# Quad_FC_V10_3.net
KiCad netlist of a schematic drawn in Altium Designer
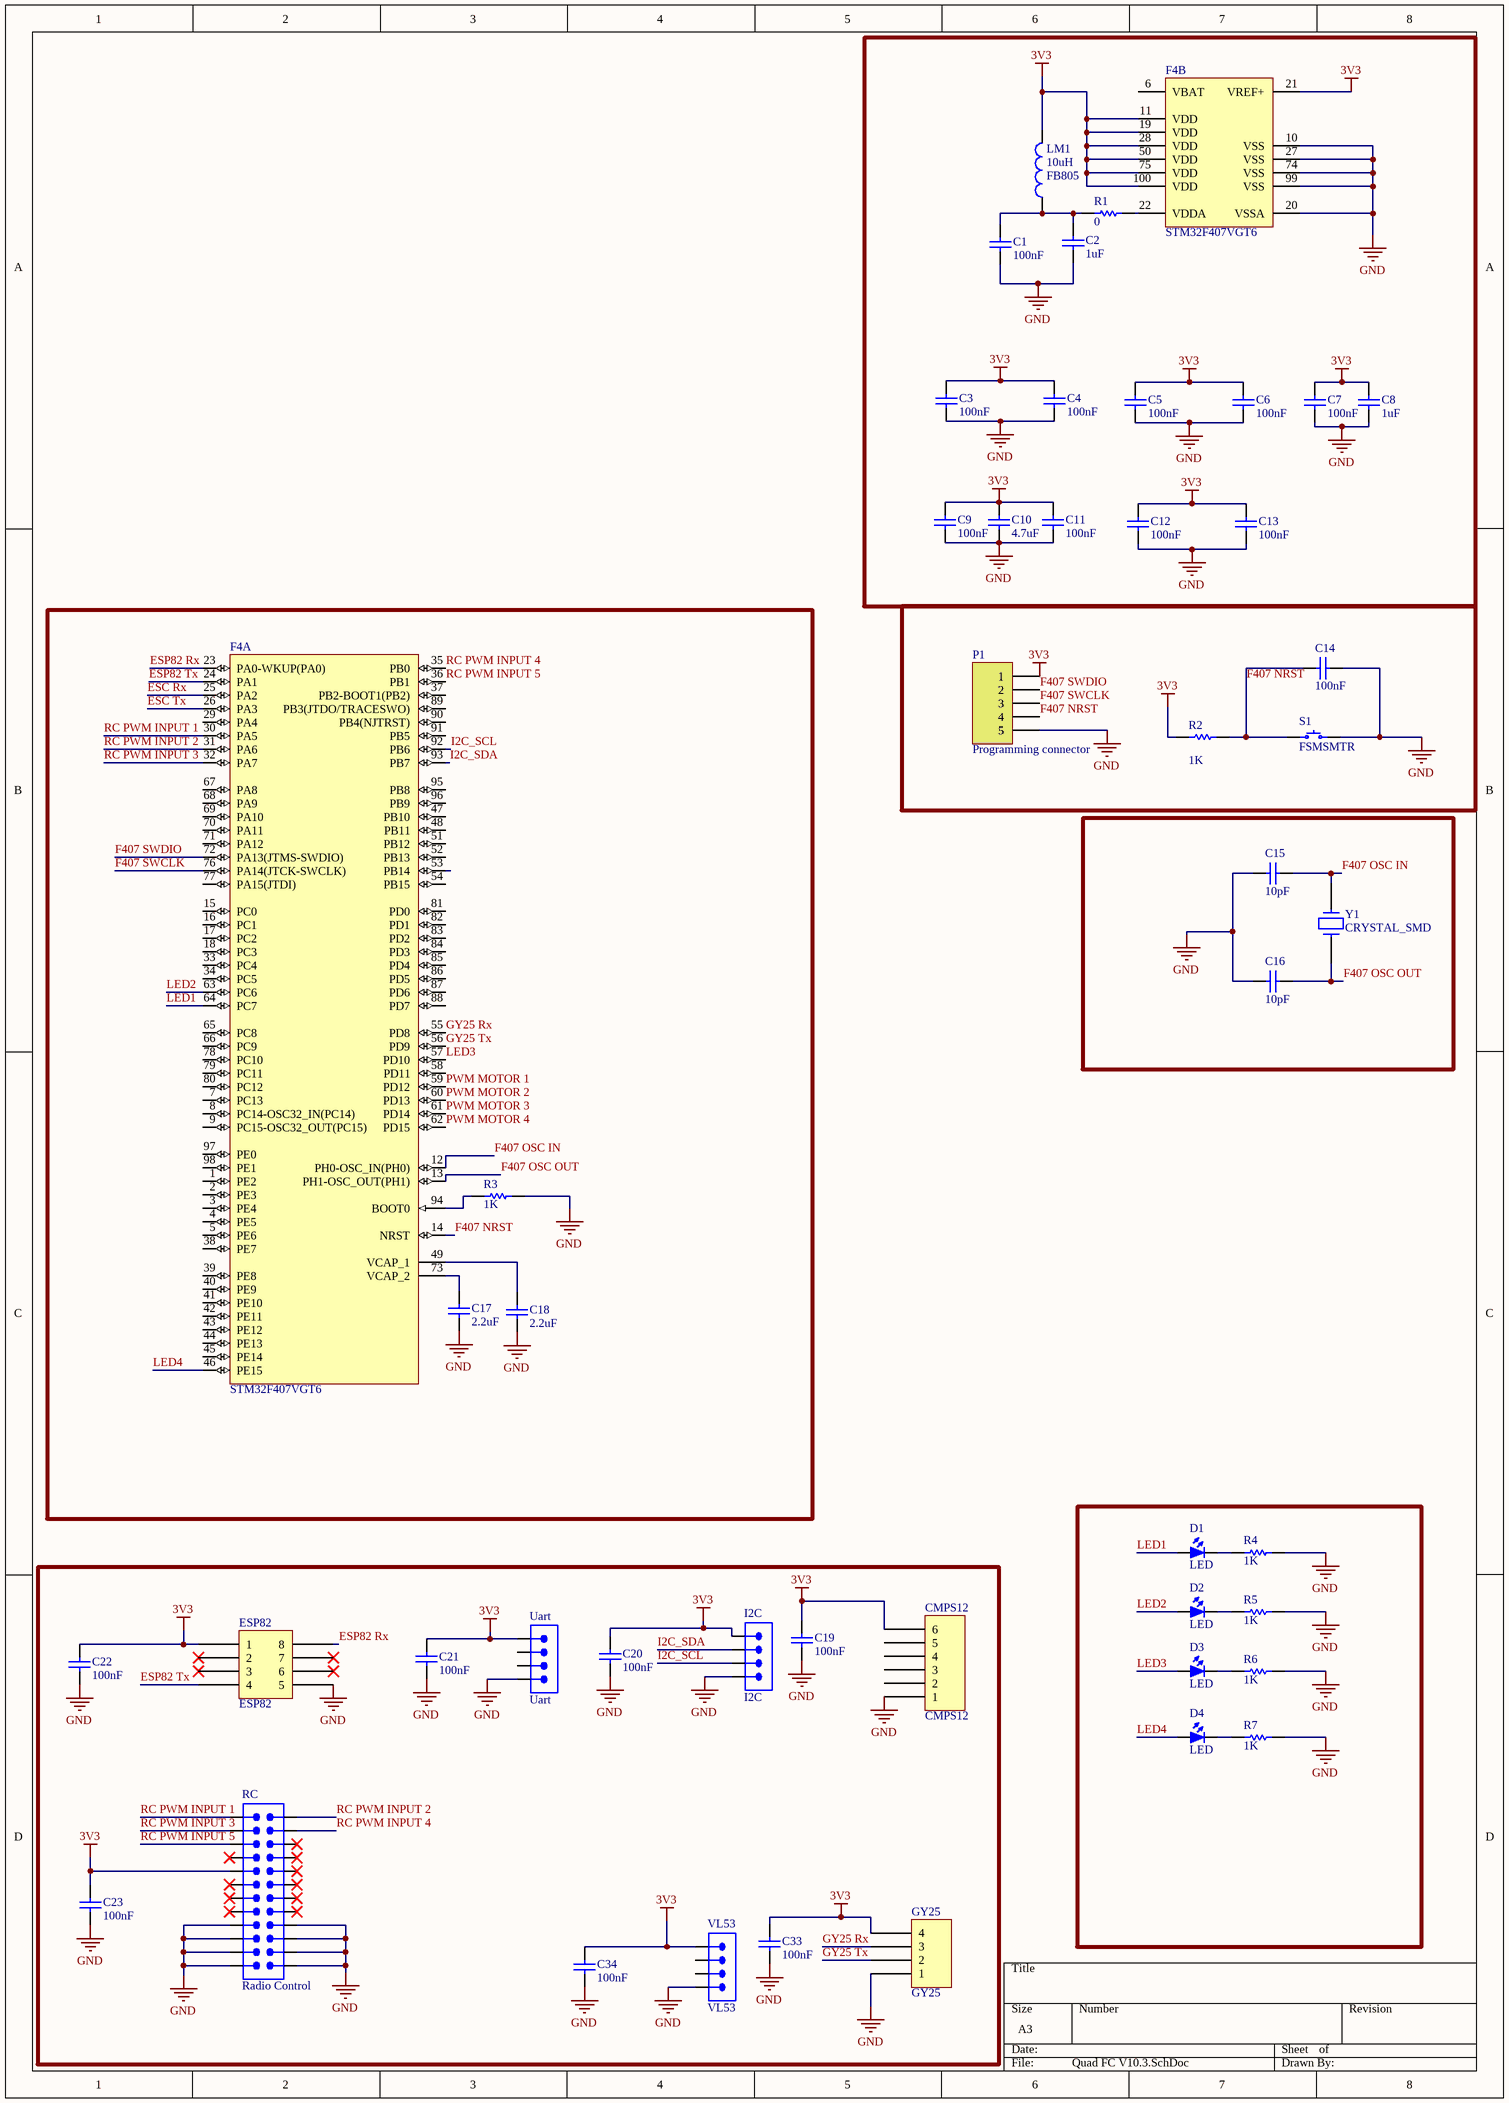
[diagram p0: Quad FC V10.3.SchDoc]

(export (version "E")
  (design (tool "Eeschema 10.0.6"))
  (components
    (comp (ref "C1")
      (value "100nF")
      (footprint "CAP0603")
      (description "F407VET6 Power CAP")
      (fields (field (name "DESIGNER") "Abbas Basereh"))
      (libsource (lib "2017AbbasBasereh9365731239 -ver1") (part "CAP SMD PACKAGE"))
    )
    (comp (ref "C2")
      (value "1uF")
      (footprint "CAP0603")
      (description "F407VET6 Power CAP")
      (fields (field (name "DESIGNER") "Abbas Basereh"))
      (libsource (lib "2017AbbasBasereh9365731239 -ver1") (part "CAP SMD PACKAGE"))
    )
    (comp (ref "C3")
      (value "100nF")
      (footprint "CAP0603")
      (description "F407VET6 Power CAP")
      (fields (field (name "DESIGNER") "Abbas Basereh"))
      (libsource (lib "2017AbbasBasereh9365731239 -ver1") (part "CAP SMD PACKAGE"))
    )
    (comp (ref "C4")
      (value "100nF")
      (footprint "CAP0603")
      (description "F407VET6 Power CAP")
      (fields (field (name "DESIGNER") "Abbas Basereh"))
      (libsource (lib "2017AbbasBasereh9365731239 -ver1") (part "CAP SMD PACKAGE"))
    )
    (comp (ref "C5")
      (value "100nF")
      (footprint "CAP0603")
      (description "F407VET6 Power CAP")
      (fields (field (name "DESIGNER") "Abbas Basereh"))
      (libsource (lib "2017AbbasBasereh9365731239 -ver1") (part "CAP SMD PACKAGE"))
    )
    (comp (ref "C6")
      (value "100nF")
      (footprint "CAP0603")
      (description "F407VET6 Power CAP")
      (fields (field (name "DESIGNER") "Abbas Basereh"))
      (libsource (lib "2017AbbasBasereh9365731239 -ver1") (part "CAP SMD PACKAGE"))
    )
    (comp (ref "C7")
      (value "100nF")
      (footprint "CAP0603")
      (description "F407VET6 Power CAP")
      (fields (field (name "DESIGNER") "Abbas Basereh"))
      (libsource (lib "2017AbbasBasereh9365731239 -ver1") (part "CAP SMD PACKAGE"))
    )
    (comp (ref "C8")
      (value "1uF")
      (footprint "CAP0603")
      (description "F407VET6 Power CAP")
      (fields (field (name "DESIGNER") "Abbas Basereh"))
      (libsource (lib "2017AbbasBasereh9365731239 -ver1") (part "CAP SMD PACKAGE"))
    )
    (comp (ref "C9")
      (value "100nF")
      (footprint "CAP0603")
      (description "F407VET6 Power CAP")
      (fields (field (name "DESIGNER") "Abbas Basereh"))
      (libsource (lib "2017AbbasBasereh9365731239 -ver1") (part "CAP SMD PACKAGE"))
    )
    (comp (ref "C10")
      (value "4.7uF")
      (footprint "CAP0603")
      (description "F407VET6 Power CAP")
      (fields (field (name "DESIGNER") "Abbas Basereh"))
      (libsource (lib "2017AbbasBasereh9365731239 -ver1") (part "CAP SMD PACKAGE"))
    )
    (comp (ref "C11")
      (value "100nF")
      (footprint "CAP0603")
      (description "F407VET6 Power CAP")
      (fields (field (name "DESIGNER") "Abbas Basereh"))
      (libsource (lib "2017AbbasBasereh9365731239 -ver1") (part "CAP SMD PACKAGE"))
    )
    (comp (ref "C12")
      (value "100nF")
      (footprint "CAP0603")
      (description "F407VET6 Power CAP")
      (fields (field (name "DESIGNER") "Abbas Basereh"))
      (libsource (lib "2017AbbasBasereh9365731239 -ver1") (part "CAP SMD PACKAGE"))
    )
    (comp (ref "C13")
      (value "100nF")
      (footprint "CAP0603")
      (description "F407VET6 Power CAP")
      (fields (field (name "DESIGNER") "Abbas Basereh"))
      (libsource (lib "2017AbbasBasereh9365731239 -ver1") (part "CAP SMD PACKAGE"))
    )
    (comp (ref "C14")
      (value "100nF")
      (footprint "CAP0603")
      (description "F407VET6 Power CAP")
      (fields (field (name "DESIGNER") "Abbas Basereh"))
      (libsource (lib "2017AbbasBasereh9365731239 -ver1") (part "CAP SMD PACKAGE"))
    )
    (comp (ref "C15")
      (value "10pF")
      (footprint "CAP0603")
      (description "F407VET6 Power CAP")
      (fields (field (name "DESIGNER") "Abbas Basereh"))
      (libsource (lib "2017AbbasBasereh9365731239 -ver1") (part "CAP SMD PACKAGE"))
    )
    (comp (ref "C16")
      (value "10pF")
      (footprint "CAP0603")
      (description "F407VET6 Power CAP")
      (fields (field (name "DESIGNER") "Abbas Basereh"))
      (libsource (lib "2017AbbasBasereh9365731239 -ver1") (part "CAP SMD PACKAGE"))
    )
    (comp (ref "C17")
      (value "2.2uF")
      (footprint "CAP0603")
      (description "F407VET6 Power CAP")
      (fields (field (name "DESIGNER") "Abbas Basereh"))
      (libsource (lib "2017AbbasBasereh9365731239 -ver1") (part "CAP SMD PACKAGE"))
    )
    (comp (ref "C18")
      (value "2.2uF")
      (footprint "CAP0603")
      (description "F407VET6 Power CAP")
      (fields (field (name "DESIGNER") "Abbas Basereh"))
      (libsource (lib "2017AbbasBasereh9365731239 -ver1") (part "CAP SMD PACKAGE"))
    )
    (comp (ref "C19")
      (value "100nF")
      (footprint "CAP0603")
      (description "F407VET6 Power CAP")
      (fields (field (name "DESIGNER") "Abbas Basereh"))
      (libsource (lib "2017AbbasBasereh9365731239 -ver1") (part "CAP SMD PACKAGE"))
    )
    (comp (ref "C20")
      (value "100nF")
      (footprint "CAP0603")
      (description "F407VET6 Power CAP")
      (fields (field (name "DESIGNER") "Abbas Basereh"))
      (libsource (lib "2017AbbasBasereh9365731239 -ver1") (part "CAP SMD PACKAGE"))
    )
    (comp (ref "C21")
      (value "100nF")
      (footprint "CAP0603")
      (description "F407VET6 Power CAP")
      (fields (field (name "DESIGNER") "Abbas Basereh"))
      (libsource (lib "2017AbbasBasereh9365731239 -ver1") (part "CAP SMD PACKAGE"))
    )
    (comp (ref "C22")
      (value "100nF")
      (footprint "CAP0603")
      (description "F407VET6 Power CAP")
      (fields (field (name "DESIGNER") "Abbas Basereh"))
      (libsource (lib "2017AbbasBasereh9365731239 -ver1") (part "CAP SMD PACKAGE"))
    )
    (comp (ref "C23")
      (value "100nF")
      (footprint "CAP0603")
      (description "F407VET6 Power CAP")
      (fields (field (name "DESIGNER") "Abbas Basereh"))
      (libsource (lib "2017AbbasBasereh9365731239 -ver1") (part "CAP SMD PACKAGE"))
    )
    (comp (ref "C33")
      (value "100nF")
      (footprint "CAP0603")
      (description "F407VET6 Power CAP")
      (fields (field (name "DESIGNER") "Abbas Basereh"))
      (libsource (lib "2017AbbasBasereh9365731239 -ver1") (part "CAP SMD PACKAGE"))
    )
    (comp (ref "C34")
      (value "100nF")
      (footprint "CAP0603")
      (description "F407VET6 Power CAP")
      (fields (field (name "DESIGNER") "Abbas Basereh"))
      (libsource (lib "2017AbbasBasereh9365731239 -ver1") (part "CAP SMD PACKAGE"))
    )
    (comp (ref "CMPS12")
      (value "CMPS12")
      (footprint "SAMTEC SSW-106-03-T-S")
      (description "CONN RCPT 6POS 0.1 TIN PCB")
      (fields (field (name "PART NUMBER") "SSW-106-03-T-S") (field (name "MANUFACTURER") "Samtec Inc."))
      (libsource (lib "Celestial Altium Library - altium_library (1)") (part "6 Pin"))
    )
    (comp (ref "D1")
      (value "LED")
      (footprint "0603 - LED")
      (description "Led")
      (fields (field (name "PUBLISHER") "Altium Limited"))
      (libsource (lib "Sajad_Altium_Library") (part "LED"))
    )
    (comp (ref "D2")
      (value "LED")
      (footprint "0603 - LED")
      (description "Led")
      (fields (field (name "PUBLISHER") "Altium Limited"))
      (libsource (lib "Sajad_Altium_Library") (part "LED"))
    )
    (comp (ref "D3")
      (value "LED")
      (footprint "0603 - LED")
      (description "Led")
      (fields (field (name "PUBLISHER") "Altium Limited"))
      (libsource (lib "Sajad_Altium_Library") (part "LED"))
    )
    (comp (ref "D4")
      (value "LED")
      (footprint "0603 - LED")
      (description "Led")
      (fields (field (name "PUBLISHER") "Altium Limited"))
      (libsource (lib "Sajad_Altium_Library") (part "LED"))
    )
    (comp (ref "ESP82")
      (value "ESP82")
      (footprint "HARWIN M20-7830445")
      (description "CONN RCPT 8POS 0.1 GOLD PCB")
      (fields (field (name "PART NUMBER") "M20-7830442") (field (name "MANUFACTURER") "Harwin Inc."))
      (libsource (lib "Celestial Altium Library - altium_library (1)") (part "2X4 PIN DU"))
    )
    (comp (ref "F4")
      (value "STM32F407VGT6")
      (footprint "STM-LQFP100_N")
      (fields (field (name "MANUFACTURER") "STMicroelectronics"))
      (libsource (lib "STMicroelectronics STM32 F4") (part "STM32F407VGT6"))
    )
    (comp (ref "GY25")
      (value "GY25")
      (footprint "SAMTEC SSW-104-03-T-S")
      (description "CONN RCPT 4POS 0.1 TIN PCB")
      (fields (field (name "PART NUMBER") "SSW-104-03-T-S") (field (name "MANUFACTURER") "Samtec Inc."))
      (libsource (lib "Celestial Altium Library - altium_library (1)") (part "4 Pin"))
    )
    (comp (ref "I2C")
      (value "I2C")
      (footprint "JST BM04B-SURS-TF")
      (description "Male Header 1X04")
      (libsource (lib "SJ Sockets & Connectors") (part "MHDR_1X04"))
    )
    (comp (ref "LM1")
      (value "10uH")
      (footprint "0805L")
      (description "Inductor")
      (fields (field (name "ALTIUM_VALUE") "FB805") (field (name "PUBLISHER") "Altium Limited"))
      (libsource (lib "2017AbbasBasereh9365731239 -ver1") (part "L SMA 0.25W"))
    )
    (comp (ref "P1")
      (value "Programming connector")
      (footprint "Connector1X5")
      (description "Connector, 5-Pin2.5mm")
      (fields (field (name "PUBLISHER") "Altium Limited"))
      (libsource (lib "Sajad_Altium_Library") (part "Connector1x5"))
    )
    (comp (ref "R1")
      (value "0")
      (footprint "RES0603")
      (description "TOTAL SMD RESISTOR PACK")
      (fields (field (name "DESIGNER") "Abbas Basereh"))
      (libsource (lib "2017AbbasBasereh9365731239 -ver1") (part "RES SMD PACKAGE"))
    )
    (comp (ref "R2")
      (value "1K")
      (footprint "RES0603")
      (description "TOTAL SMD RESISTOR PACK")
      (fields (field (name "DESIGNER") "Abbas Basereh"))
      (libsource (lib "2017AbbasBasereh9365731239 -ver1") (part "RES SMD PACKAGE"))
    )
    (comp (ref "R3")
      (value "1K")
      (footprint "RES0603")
      (description "TOTAL SMD RESISTOR PACK")
      (fields (field (name "DESIGNER") "Abbas Basereh"))
      (libsource (lib "2017AbbasBasereh9365731239 -ver1") (part "RES SMD PACKAGE"))
    )
    (comp (ref "R4")
      (value "1K")
      (footprint "RES0603")
      (description "TOTAL SMD RESISTOR PACK")
      (fields (field (name "DESIGNER") "Abbas Basereh"))
      (libsource (lib "2017AbbasBasereh9365731239 -ver1") (part "RES SMD PACKAGE"))
    )
    (comp (ref "R5")
      (value "1K")
      (footprint "RES0603")
      (description "TOTAL SMD RESISTOR PACK")
      (fields (field (name "DESIGNER") "Abbas Basereh"))
      (libsource (lib "2017AbbasBasereh9365731239 -ver1") (part "RES SMD PACKAGE"))
    )
    (comp (ref "R6")
      (value "1K")
      (footprint "RES0603")
      (description "TOTAL SMD RESISTOR PACK")
      (fields (field (name "DESIGNER") "Abbas Basereh"))
      (libsource (lib "2017AbbasBasereh9365731239 -ver1") (part "RES SMD PACKAGE"))
    )
    (comp (ref "R7")
      (value "1K")
      (footprint "RES0603")
      (description "TOTAL SMD RESISTOR PACK")
      (fields (field (name "DESIGNER") "Abbas Basereh"))
      (libsource (lib "2017AbbasBasereh9365731239 -ver1") (part "RES SMD PACKAGE"))
    )
    (comp (ref "RC")
      (value "Radio Control")
      (footprint "HEADER8X3:HEADER8X3")
      (description "Male Header 2X12")
      (libsource (lib "SJ Sockets & Connectors") (part "MHDR_2X12"))
    )
    (comp (ref "S1")
      (value "FSMSMTR")
      (footprint "TE FSMSMTR")
      (description "SWITCH TACTILE SPST-NO 0.05A 24V")
      (fields (field (name "MANUFACTURER") "TE Connectivity ALCOSWITCH Switches"))
      (libsource (lib "Celestial Altium Library - altium_library (1)") (part "SPST-NO 2 PIN"))
    )
    (comp (ref "Uart")
      (value "Uart")
      (footprint "JST BM04B-SURS-TF")
      (description "Male Header 1X04")
      (libsource (lib "SJ Sockets & Connectors") (part "MHDR_1X04"))
    )
    (comp (ref "VL53")
      (value "VL53")
      (footprint "JST BM04B-SURS-TF")
      (description "Male Header 1X04")
      (libsource (lib "SJ Sockets & Connectors") (part "MHDR_1X04"))
    )
    (comp (ref "Y1")
      (value "CRYSTAL_SMD")
      (footprint "My_Crystal - SMD")
      (description "Crystal")
      (libsource (lib "AMINLIB") (part "CRYSTAL_SMD"))
    )
  )
  (nets
    (net (code "1") (name "/ESC Rx") (class "Default")
      (node (ref "F4") (pin "25") (pinfunction "PA2_25") (pintype "bidirectional"))
    )
    (net (code "2") (name "/ESC Tx") (class "Default")
      (node (ref "F4") (pin "26") (pinfunction "PA3_26") (pintype "bidirectional"))
    )
    (net (code "3") (name "/ESP82 Rx") (class "Default")
      (node (ref "ESP82") (pin "8") (pinfunction "8_8") (pintype "passive"))
      (node (ref "F4") (pin "23") (pinfunction "PA0-WKUP(PA0)_23") (pintype "bidirectional"))
    )
    (net (code "4") (name "/ESP82 Tx") (class "Default")
      (node (ref "ESP82") (pin "4") (pinfunction "4_4") (pintype "passive"))
      (node (ref "F4") (pin "24") (pinfunction "PA1_24") (pintype "bidirectional"))
    )
    (net (code "5") (name "/F407 NRST") (class "Default")
      (node (ref "C14") (pin "1") (pinfunction "1_1") (pintype "passive"))
      (node (ref "F4") (pin "14") (pinfunction "NRST_14") (pintype "bidirectional"))
      (node (ref "P1") (pin "4") (pinfunction "4_4") (pintype "passive"))
      (node (ref "R2") (pin "2") (pinfunction "2_2") (pintype "passive"))
      (node (ref "S1") (pin "1") (pinfunction "1_1") (pintype "passive"))
    )
    (net (code "6") (name "/F407 OSC IN") (class "Default")
      (node (ref "C15") (pin "2") (pinfunction "2_2") (pintype "passive"))
      (node (ref "F4") (pin "12") (pinfunction "PH0-OSC_IN(PH0)_12") (pintype "bidirectional"))
      (node (ref "Y1") (pin "2") (pinfunction "2_2") (pintype "passive"))
    )
    (net (code "7") (name "/F407 OSC OUT") (class "Default")
      (node (ref "C16") (pin "1") (pinfunction "1_1") (pintype "passive"))
      (node (ref "F4") (pin "13") (pinfunction "PH1-OSC_OUT(PH1)_13") (pintype "bidirectional"))
      (node (ref "Y1") (pin "1") (pinfunction "1_1") (pintype "passive"))
    )
    (net (code "8") (name "/F407 SWCLK") (class "Default")
      (node (ref "F4") (pin "76") (pinfunction "PA14(JTCK-SWCLK)_76") (pintype "bidirectional"))
      (node (ref "P1") (pin "3") (pinfunction "3_3") (pintype "passive"))
    )
    (net (code "9") (name "/F407 SWDIO") (class "Default")
      (node (ref "F4") (pin "72") (pinfunction "PA13(JTMS-SWDIO)_72") (pintype "bidirectional"))
      (node (ref "P1") (pin "2") (pinfunction "2_2") (pintype "passive"))
    )
    (net (code "10") (name "/GY25 Rx") (class "Default")
      (node (ref "F4") (pin "55") (pinfunction "PD8_55") (pintype "bidirectional"))
      (node (ref "GY25") (pin "3") (pinfunction "3_3") (pintype "passive"))
    )
    (net (code "11") (name "/GY25 Tx") (class "Default")
      (node (ref "F4") (pin "56") (pinfunction "PD9_56") (pintype "bidirectional"))
      (node (ref "GY25") (pin "2") (pinfunction "2_2") (pintype "passive"))
    )
    (net (code "12") (name "/I2C_SCL") (class "Default")
      (node (ref "F4") (pin "92") (pinfunction "PB6_92") (pintype "bidirectional"))
      (node (ref "I2C") (pin "3") (pinfunction "3_3") (pintype "passive"))
    )
    (net (code "13") (name "/I2C_SDA") (class "Default")
      (node (ref "F4") (pin "93") (pinfunction "PB7_93") (pintype "bidirectional"))
      (node (ref "I2C") (pin "2") (pinfunction "2_2") (pintype "passive"))
    )
    (net (code "14") (name "/LED1") (class "Default")
      (node (ref "D1") (pin "1") (pinfunction "A_1") (pintype "passive"))
      (node (ref "F4") (pin "64") (pinfunction "PC7_64") (pintype "bidirectional"))
    )
    (net (code "15") (name "/LED2") (class "Default")
      (node (ref "D2") (pin "1") (pinfunction "A_1") (pintype "passive"))
      (node (ref "F4") (pin "63") (pinfunction "PC6_63") (pintype "bidirectional"))
    )
    (net (code "16") (name "/LED3") (class "Default")
      (node (ref "D3") (pin "1") (pinfunction "A_1") (pintype "passive"))
      (node (ref "F4") (pin "57") (pinfunction "PD10_57") (pintype "bidirectional"))
    )
    (net (code "17") (name "/LED4") (class "Default")
      (node (ref "D4") (pin "1") (pinfunction "A_1") (pintype "passive"))
      (node (ref "F4") (pin "46") (pinfunction "PE15_46") (pintype "bidirectional"))
    )
    (net (code "18") (name "/PWM MOTOR 1") (class "Default")
      (node (ref "F4") (pin "59") (pinfunction "PD12_59") (pintype "bidirectional"))
    )
    (net (code "19") (name "/PWM MOTOR 2") (class "Default")
      (node (ref "F4") (pin "60") (pinfunction "PD13_60") (pintype "bidirectional"))
    )
    (net (code "20") (name "/PWM MOTOR 3") (class "Default")
      (node (ref "F4") (pin "61") (pinfunction "PD14_61") (pintype "bidirectional"))
    )
    (net (code "21") (name "/PWM MOTOR 4") (class "Default")
      (node (ref "F4") (pin "62") (pinfunction "PD15_62") (pintype "bidirectional"))
    )
    (net (code "22") (name "/RC PWM INPUT 1") (class "Default")
      (node (ref "F4") (pin "30") (pinfunction "PA5_30") (pintype "bidirectional"))
      (node (ref "RC") (pin "1") (pinfunction "1_1") (pintype "passive"))
    )
    (net (code "23") (name "/RC PWM INPUT 2") (class "Default")
      (node (ref "F4") (pin "31") (pinfunction "PA6_31") (pintype "bidirectional"))
      (node (ref "RC") (pin "2") (pinfunction "2_2") (pintype "passive"))
    )
    (net (code "24") (name "/RC PWM INPUT 3") (class "Default")
      (node (ref "F4") (pin "32") (pinfunction "PA7_32") (pintype "bidirectional"))
      (node (ref "RC") (pin "3") (pinfunction "3_3") (pintype "passive"))
    )
    (net (code "25") (name "/RC PWM INPUT 4") (class "Default")
      (node (ref "F4") (pin "35") (pinfunction "PB0_35") (pintype "bidirectional"))
      (node (ref "RC") (pin "4") (pinfunction "4_4") (pintype "passive"))
    )
    (net (code "26") (name "/RC PWM INPUT 5") (class "Default")
      (node (ref "F4") (pin "36") (pinfunction "PB1_36") (pintype "bidirectional"))
      (node (ref "RC") (pin "5") (pinfunction "5_5") (pintype "passive"))
    )
    (net (code "27") (name "3V3") (class "Default")
      (node (ref "C10") (pin "2") (pinfunction "2_2") (pintype "passive"))
      (node (ref "C11") (pin "2") (pinfunction "2_2") (pintype "passive"))
      (node (ref "C12") (pin "2") (pinfunction "2_2") (pintype "passive"))
      (node (ref "C13") (pin "2") (pinfunction "2_2") (pintype "passive"))
      (node (ref "C19") (pin "1") (pinfunction "1_1") (pintype "passive"))
      (node (ref "C20") (pin "1") (pinfunction "1_1") (pintype "passive"))
      (node (ref "C21") (pin "1") (pinfunction "1_1") (pintype "passive"))
      (node (ref "C22") (pin "1") (pinfunction "1_1") (pintype "passive"))
      (node (ref "C23") (pin "1") (pinfunction "1_1") (pintype "passive"))
      (node (ref "C3") (pin "2") (pinfunction "2_2") (pintype "passive"))
      (node (ref "C33") (pin "1") (pinfunction "1_1") (pintype "passive"))
      (node (ref "C34") (pin "1") (pinfunction "1_1") (pintype "passive"))
      (node (ref "C4") (pin "2") (pinfunction "2_2") (pintype "passive"))
      (node (ref "C5") (pin "2") (pinfunction "2_2") (pintype "passive"))
      (node (ref "C6") (pin "2") (pinfunction "2_2") (pintype "passive"))
      (node (ref "C7") (pin "1") (pinfunction "1_1") (pintype "passive"))
      (node (ref "C8") (pin "1") (pinfunction "1_1") (pintype "passive"))
      (node (ref "C9") (pin "2") (pinfunction "2_2") (pintype "passive"))
      (node (ref "CMPS12") (pin "6") (pinfunction "6_6") (pintype "passive"))
      (node (ref "ESP82") (pin "1") (pinfunction "1_1") (pintype "passive"))
      (node (ref "F4") (pin "100") (pinfunction "VDD_100") (pintype "power_in"))
      (node (ref "F4") (pin "11") (pinfunction "VDD_11") (pintype "power_in"))
      (node (ref "F4") (pin "19") (pinfunction "VDD_19") (pintype "power_in"))
      (node (ref "F4") (pin "21") (pinfunction "VREF+_21") (pintype "power_in"))
      (node (ref "F4") (pin "28") (pinfunction "VDD_28") (pintype "power_in"))
      (node (ref "F4") (pin "50") (pinfunction "VDD_50") (pintype "power_in"))
      (node (ref "F4") (pin "75") (pinfunction "VDD_75") (pintype "power_in"))
      (node (ref "GY25") (pin "4") (pinfunction "4_4") (pintype "passive"))
      (node (ref "I2C") (pin "1") (pinfunction "1_1") (pintype "passive"))
      (node (ref "LM1") (pin "2") (pinfunction "2_2") (pintype "passive"))
      (node (ref "P1") (pin "1") (pinfunction "1_1") (pintype "passive"))
      (node (ref "R2") (pin "1") (pinfunction "1_1") (pintype "passive"))
      (node (ref "RC") (pin "9") (pinfunction "9_9") (pintype "passive"))
      (node (ref "Uart") (pin "1") (pinfunction "1_1") (pintype "passive"))
      (node (ref "VL53") (pin "1") (pinfunction "1_1") (pintype "passive"))
    )
    (net (code "28") (name "GND") (class "Default")
      (node (ref "C1") (pin "1") (pinfunction "1_1") (pintype "passive"))
      (node (ref "C10") (pin "1") (pinfunction "1_1") (pintype "passive"))
      (node (ref "C11") (pin "1") (pinfunction "1_1") (pintype "passive"))
      (node (ref "C12") (pin "1") (pinfunction "1_1") (pintype "passive"))
      (node (ref "C13") (pin "1") (pinfunction "1_1") (pintype "passive"))
      (node (ref "C14") (pin "2") (pinfunction "2_2") (pintype "passive"))
      (node (ref "C15") (pin "1") (pinfunction "1_1") (pintype "passive"))
      (node (ref "C16") (pin "2") (pinfunction "2_2") (pintype "passive"))
      (node (ref "C17") (pin "2") (pinfunction "2_2") (pintype "passive"))
      (node (ref "C18") (pin "2") (pinfunction "2_2") (pintype "passive"))
      (node (ref "C19") (pin "2") (pinfunction "2_2") (pintype "passive"))
      (node (ref "C2") (pin "1") (pinfunction "1_1") (pintype "passive"))
      (node (ref "C20") (pin "2") (pinfunction "2_2") (pintype "passive"))
      (node (ref "C21") (pin "2") (pinfunction "2_2") (pintype "passive"))
      (node (ref "C22") (pin "2") (pinfunction "2_2") (pintype "passive"))
      (node (ref "C23") (pin "2") (pinfunction "2_2") (pintype "passive"))
      (node (ref "C3") (pin "1") (pinfunction "1_1") (pintype "passive"))
      (node (ref "C33") (pin "2") (pinfunction "2_2") (pintype "passive"))
      (node (ref "C34") (pin "2") (pinfunction "2_2") (pintype "passive"))
      (node (ref "C4") (pin "1") (pinfunction "1_1") (pintype "passive"))
      (node (ref "C5") (pin "1") (pinfunction "1_1") (pintype "passive"))
      (node (ref "C6") (pin "1") (pinfunction "1_1") (pintype "passive"))
      (node (ref "C7") (pin "2") (pinfunction "2_2") (pintype "passive"))
      (node (ref "C8") (pin "2") (pinfunction "2_2") (pintype "passive"))
      (node (ref "C9") (pin "1") (pinfunction "1_1") (pintype "passive"))
      (node (ref "CMPS12") (pin "1") (pinfunction "1_1") (pintype "passive"))
      (node (ref "ESP82") (pin "5") (pinfunction "5_5") (pintype "passive"))
      (node (ref "F4") (pin "10") (pinfunction "VSS_10") (pintype "power_in"))
      (node (ref "F4") (pin "20") (pinfunction "VSSA_20") (pintype "power_in"))
      (node (ref "F4") (pin "27") (pinfunction "VSS_27") (pintype "power_in"))
      (node (ref "F4") (pin "74") (pinfunction "VSS_74") (pintype "power_in"))
      (node (ref "F4") (pin "99") (pinfunction "VSS_99") (pintype "power_in"))
      (node (ref "GY25") (pin "1") (pinfunction "1_1") (pintype "passive"))
      (node (ref "I2C") (pin "4") (pinfunction "4_4") (pintype "passive"))
      (node (ref "P1") (pin "5") (pinfunction "5_5") (pintype "passive"))
      (node (ref "R3") (pin "2") (pinfunction "2_2") (pintype "passive"))
      (node (ref "R4") (pin "2") (pinfunction "2_2") (pintype "passive"))
      (node (ref "R5") (pin "2") (pinfunction "2_2") (pintype "passive"))
      (node (ref "R6") (pin "2") (pinfunction "2_2") (pintype "passive"))
      (node (ref "R7") (pin "2") (pinfunction "2_2") (pintype "passive"))
      (node (ref "RC") (pin "17") (pinfunction "17_17") (pintype "passive"))
      (node (ref "RC") (pin "18") (pinfunction "18_18") (pintype "passive"))
      (node (ref "RC") (pin "19") (pinfunction "19_19") (pintype "passive"))
      (node (ref "RC") (pin "20") (pinfunction "20_20") (pintype "passive"))
      (node (ref "RC") (pin "21") (pinfunction "21_21") (pintype "passive"))
      (node (ref "RC") (pin "22") (pinfunction "22_22") (pintype "passive"))
      (node (ref "RC") (pin "23") (pinfunction "23_23") (pintype "passive"))
      (node (ref "RC") (pin "24") (pinfunction "24_24") (pintype "passive"))
      (node (ref "S1") (pin "2") (pinfunction "2_2") (pintype "passive"))
      (node (ref "Uart") (pin "4") (pinfunction "4_4") (pintype "passive"))
      (node (ref "VL53") (pin "4") (pinfunction "4_4") (pintype "passive"))
    )
    (net (code "29") (name "Net-(C1-Pad2)") (class "Default")
      (node (ref "C1") (pin "2") (pinfunction "2_2") (pintype "passive"))
      (node (ref "C2") (pin "2") (pinfunction "2_2") (pintype "passive"))
      (node (ref "LM1") (pin "1") (pinfunction "1_1") (pintype "passive"))
      (node (ref "R1") (pin "1") (pinfunction "1_1") (pintype "passive"))
    )
    (net (code "30") (name "Net-(D1-K)") (class "Default")
      (node (ref "D1") (pin "2") (pinfunction "K_2") (pintype "passive"))
      (node (ref "R4") (pin "1") (pinfunction "1_1") (pintype "passive"))
    )
    (net (code "31") (name "Net-(D2-K)") (class "Default")
      (node (ref "D2") (pin "2") (pinfunction "K_2") (pintype "passive"))
      (node (ref "R5") (pin "1") (pinfunction "1_1") (pintype "passive"))
    )
    (net (code "32") (name "Net-(D3-K)") (class "Default")
      (node (ref "D3") (pin "2") (pinfunction "K_2") (pintype "passive"))
      (node (ref "R6") (pin "1") (pinfunction "1_1") (pintype "passive"))
    )
    (net (code "33") (name "Net-(D4-K)") (class "Default")
      (node (ref "D4") (pin "2") (pinfunction "K_2") (pintype "passive"))
      (node (ref "R7") (pin "1") (pinfunction "1_1") (pintype "passive"))
    )
    (net (code "34") (name "Net-(F4A-BOOT0)") (class "Default")
      (node (ref "F4") (pin "94") (pinfunction "BOOT0_94") (pintype "input"))
      (node (ref "R3") (pin "1") (pinfunction "1_1") (pintype "passive"))
    )
    (net (code "35") (name "Net-(F4A-VCAP_1)") (class "Default")
      (node (ref "C18") (pin "1") (pinfunction "1_1") (pintype "passive"))
      (node (ref "F4") (pin "49") (pinfunction "VCAP_1_49") (pintype "power_in"))
    )
    (net (code "36") (name "Net-(F4A-VCAP_2)") (class "Default")
      (node (ref "C17") (pin "1") (pinfunction "1_1") (pintype "passive"))
      (node (ref "F4") (pin "73") (pinfunction "VCAP_2_73") (pintype "power_in"))
    )
    (net (code "37") (name "Net-(F4B-VDDA)") (class "Default")
      (node (ref "F4") (pin "22") (pinfunction "VDDA_22") (pintype "power_in"))
      (node (ref "R1") (pin "2") (pinfunction "2_2") (pintype "passive"))
    )
    (net (code "38") (name "unconnected-(CMPS12-Pad2)") (class "Default")
      (node (ref "CMPS12") (pin "2") (pinfunction "2_2") (pintype "passive"))
    )
    (net (code "39") (name "unconnected-(CMPS12-Pad3)") (class "Default")
      (node (ref "CMPS12") (pin "3") (pinfunction "3_3") (pintype "passive"))
    )
    (net (code "40") (name "unconnected-(CMPS12-Pad4)") (class "Default")
      (node (ref "CMPS12") (pin "4") (pinfunction "4_4") (pintype "passive"))
    )
    (net (code "41") (name "unconnected-(CMPS12-Pad5)") (class "Default")
      (node (ref "CMPS12") (pin "5") (pinfunction "5_5") (pintype "passive"))
    )
    (net (code "42") (name "unconnected-(ESP82-Pad2)") (class "Default")
      (node (ref "ESP82") (pin "2") (pinfunction "2_2") (pintype "passive+no_connect"))
    )
    (net (code "43") (name "unconnected-(ESP82-Pad3)") (class "Default")
      (node (ref "ESP82") (pin "3") (pinfunction "3_3") (pintype "passive+no_connect"))
    )
    (net (code "44") (name "unconnected-(ESP82-Pad6)") (class "Default")
      (node (ref "ESP82") (pin "6") (pinfunction "6_6") (pintype "passive+no_connect"))
    )
    (net (code "45") (name "unconnected-(ESP82-Pad7)") (class "Default")
      (node (ref "ESP82") (pin "7") (pinfunction "7_7") (pintype "passive+no_connect"))
    )
    (net (code "46") (name "unconnected-(F4A-PA4-Pad29)") (class "Default")
      (node (ref "F4") (pin "29") (pinfunction "PA4_29") (pintype "bidirectional"))
    )
    (net (code "47") (name "unconnected-(F4A-PA8-Pad67)") (class "Default")
      (node (ref "F4") (pin "67") (pinfunction "PA8_67") (pintype "bidirectional"))
    )
    (net (code "48") (name "unconnected-(F4A-PA9-Pad68)") (class "Default")
      (node (ref "F4") (pin "68") (pinfunction "PA9_68") (pintype "bidirectional"))
    )
    (net (code "49") (name "unconnected-(F4A-PA10-Pad69)") (class "Default")
      (node (ref "F4") (pin "69") (pinfunction "PA10_69") (pintype "bidirectional"))
    )
    (net (code "50") (name "unconnected-(F4A-PA11-Pad70)") (class "Default")
      (node (ref "F4") (pin "70") (pinfunction "PA11_70") (pintype "bidirectional"))
    )
    (net (code "51") (name "unconnected-(F4A-PA12-Pad71)") (class "Default")
      (node (ref "F4") (pin "71") (pinfunction "PA12_71") (pintype "bidirectional"))
    )
    (net (code "52") (name "unconnected-(F4A-PA15(JTDI)-Pad77)") (class "Default")
      (node (ref "F4") (pin "77") (pinfunction "PA15(JTDI)_77") (pintype "bidirectional"))
    )
    (net (code "53") (name "unconnected-(F4A-PB2-BOOT1(PB2)-Pad37)") (class "Default")
      (node (ref "F4") (pin "37") (pinfunction "PB2-BOOT1(PB2)_37") (pintype "bidirectional"))
    )
    (net (code "54") (name "unconnected-(F4A-PB3(JTDO{slash}TRACESWO)-Pad89)") (class "Default")
      (node (ref "F4") (pin "89") (pinfunction "PB3(JTDO/TRACESWO)_89") (pintype "bidirectional"))
    )
    (net (code "55") (name "unconnected-(F4A-PB4(NJTRST)-Pad90)") (class "Default")
      (node (ref "F4") (pin "90") (pinfunction "PB4(NJTRST)_90") (pintype "bidirectional"))
    )
    (net (code "56") (name "unconnected-(F4A-PB5-Pad91)") (class "Default")
      (node (ref "F4") (pin "91") (pinfunction "PB5_91") (pintype "bidirectional"))
    )
    (net (code "57") (name "unconnected-(F4A-PB8-Pad95)") (class "Default")
      (node (ref "F4") (pin "95") (pinfunction "PB8_95") (pintype "bidirectional"))
    )
    (net (code "58") (name "unconnected-(F4A-PB9-Pad96)") (class "Default")
      (node (ref "F4") (pin "96") (pinfunction "PB9_96") (pintype "bidirectional"))
    )
    (net (code "59") (name "unconnected-(F4A-PB10-Pad47)") (class "Default")
      (node (ref "F4") (pin "47") (pinfunction "PB10_47") (pintype "bidirectional"))
    )
    (net (code "60") (name "unconnected-(F4A-PB11-Pad48)") (class "Default")
      (node (ref "F4") (pin "48") (pinfunction "PB11_48") (pintype "bidirectional"))
    )
    (net (code "61") (name "unconnected-(F4A-PB12-Pad51)") (class "Default")
      (node (ref "F4") (pin "51") (pinfunction "PB12_51") (pintype "bidirectional"))
    )
    (net (code "62") (name "unconnected-(F4A-PB13-Pad52)") (class "Default")
      (node (ref "F4") (pin "52") (pinfunction "PB13_52") (pintype "bidirectional"))
    )
    (net (code "63") (name "unconnected-(F4A-PB14-Pad53)") (class "Default")
      (node (ref "F4") (pin "53") (pinfunction "PB14_53") (pintype "bidirectional"))
    )
    (net (code "64") (name "unconnected-(F4A-PB15-Pad54)") (class "Default")
      (node (ref "F4") (pin "54") (pinfunction "PB15_54") (pintype "bidirectional"))
    )
    (net (code "65") (name "unconnected-(F4A-PC0-Pad15)") (class "Default")
      (node (ref "F4") (pin "15") (pinfunction "PC0_15") (pintype "bidirectional"))
    )
    (net (code "66") (name "unconnected-(F4A-PC1-Pad16)") (class "Default")
      (node (ref "F4") (pin "16") (pinfunction "PC1_16") (pintype "bidirectional"))
    )
    (net (code "67") (name "unconnected-(F4A-PC2-Pad17)") (class "Default")
      (node (ref "F4") (pin "17") (pinfunction "PC2_17") (pintype "bidirectional"))
    )
    (net (code "68") (name "unconnected-(F4A-PC3-Pad18)") (class "Default")
      (node (ref "F4") (pin "18") (pinfunction "PC3_18") (pintype "bidirectional"))
    )
    (net (code "69") (name "unconnected-(F4A-PC4-Pad33)") (class "Default")
      (node (ref "F4") (pin "33") (pinfunction "PC4_33") (pintype "bidirectional"))
    )
    (net (code "70") (name "unconnected-(F4A-PC5-Pad34)") (class "Default")
      (node (ref "F4") (pin "34") (pinfunction "PC5_34") (pintype "bidirectional"))
    )
    (net (code "71") (name "unconnected-(F4A-PC8-Pad65)") (class "Default")
      (node (ref "F4") (pin "65") (pinfunction "PC8_65") (pintype "bidirectional"))
    )
    (net (code "72") (name "unconnected-(F4A-PC9-Pad66)") (class "Default")
      (node (ref "F4") (pin "66") (pinfunction "PC9_66") (pintype "bidirectional"))
    )
    (net (code "73") (name "unconnected-(F4A-PC10-Pad78)") (class "Default")
      (node (ref "F4") (pin "78") (pinfunction "PC10_78") (pintype "bidirectional"))
    )
    (net (code "74") (name "unconnected-(F4A-PC11-Pad79)") (class "Default")
      (node (ref "F4") (pin "79") (pinfunction "PC11_79") (pintype "bidirectional"))
    )
    (net (code "75") (name "unconnected-(F4A-PC12-Pad80)") (class "Default")
      (node (ref "F4") (pin "80") (pinfunction "PC12_80") (pintype "bidirectional"))
    )
    (net (code "76") (name "unconnected-(F4A-PC13-Pad7)") (class "Default")
      (node (ref "F4") (pin "7") (pinfunction "PC13_7") (pintype "bidirectional"))
    )
    (net (code "77") (name "unconnected-(F4A-PC14-OSC32_IN(PC14)-Pad8)") (class "Default")
      (node (ref "F4") (pin "8") (pinfunction "PC14-OSC32_IN(PC14)_8") (pintype "bidirectional"))
    )
    (net (code "78") (name "unconnected-(F4A-PC15-OSC32_OUT(PC15)-Pad9)") (class "Default")
      (node (ref "F4") (pin "9") (pinfunction "PC15-OSC32_OUT(PC15)_9") (pintype "bidirectional"))
    )
    (net (code "79") (name "unconnected-(F4A-PD0-Pad81)") (class "Default")
      (node (ref "F4") (pin "81") (pinfunction "PD0_81") (pintype "bidirectional"))
    )
    (net (code "80") (name "unconnected-(F4A-PD1-Pad82)") (class "Default")
      (node (ref "F4") (pin "82") (pinfunction "PD1_82") (pintype "bidirectional"))
    )
    (net (code "81") (name "unconnected-(F4A-PD2-Pad83)") (class "Default")
      (node (ref "F4") (pin "83") (pinfunction "PD2_83") (pintype "bidirectional"))
    )
    (net (code "82") (name "unconnected-(F4A-PD3-Pad84)") (class "Default")
      (node (ref "F4") (pin "84") (pinfunction "PD3_84") (pintype "bidirectional"))
    )
    (net (code "83") (name "unconnected-(F4A-PD4-Pad85)") (class "Default")
      (node (ref "F4") (pin "85") (pinfunction "PD4_85") (pintype "bidirectional"))
    )
    (net (code "84") (name "unconnected-(F4A-PD5-Pad86)") (class "Default")
      (node (ref "F4") (pin "86") (pinfunction "PD5_86") (pintype "bidirectional"))
    )
    (net (code "85") (name "unconnected-(F4A-PD6-Pad87)") (class "Default")
      (node (ref "F4") (pin "87") (pinfunction "PD6_87") (pintype "bidirectional"))
    )
    (net (code "86") (name "unconnected-(F4A-PD7-Pad88)") (class "Default")
      (node (ref "F4") (pin "88") (pinfunction "PD7_88") (pintype "bidirectional"))
    )
    (net (code "87") (name "unconnected-(F4A-PD11-Pad58)") (class "Default")
      (node (ref "F4") (pin "58") (pinfunction "PD11_58") (pintype "bidirectional"))
    )
    (net (code "88") (name "unconnected-(F4A-PE0-Pad97)") (class "Default")
      (node (ref "F4") (pin "97") (pinfunction "PE0_97") (pintype "bidirectional"))
    )
    (net (code "89") (name "unconnected-(F4A-PE1-Pad98)") (class "Default")
      (node (ref "F4") (pin "98") (pinfunction "PE1_98") (pintype "bidirectional"))
    )
    (net (code "90") (name "unconnected-(F4A-PE2-Pad1)") (class "Default")
      (node (ref "F4") (pin "1") (pinfunction "PE2_1") (pintype "bidirectional"))
    )
    (net (code "91") (name "unconnected-(F4A-PE3-Pad2)") (class "Default")
      (node (ref "F4") (pin "2") (pinfunction "PE3_2") (pintype "bidirectional"))
    )
    (net (code "92") (name "unconnected-(F4A-PE4-Pad3)") (class "Default")
      (node (ref "F4") (pin "3") (pinfunction "PE4_3") (pintype "bidirectional"))
    )
    (net (code "93") (name "unconnected-(F4A-PE5-Pad4)") (class "Default")
      (node (ref "F4") (pin "4") (pinfunction "PE5_4") (pintype "bidirectional"))
    )
    (net (code "94") (name "unconnected-(F4A-PE6-Pad5)") (class "Default")
      (node (ref "F4") (pin "5") (pinfunction "PE6_5") (pintype "bidirectional"))
    )
    (net (code "95") (name "unconnected-(F4A-PE7-Pad38)") (class "Default")
      (node (ref "F4") (pin "38") (pinfunction "PE7_38") (pintype "bidirectional"))
    )
    (net (code "96") (name "unconnected-(F4A-PE8-Pad39)") (class "Default")
      (node (ref "F4") (pin "39") (pinfunction "PE8_39") (pintype "bidirectional"))
    )
    (net (code "97") (name "unconnected-(F4A-PE9-Pad40)") (class "Default")
      (node (ref "F4") (pin "40") (pinfunction "PE9_40") (pintype "bidirectional"))
    )
    (net (code "98") (name "unconnected-(F4A-PE10-Pad41)") (class "Default")
      (node (ref "F4") (pin "41") (pinfunction "PE10_41") (pintype "bidirectional"))
    )
    (net (code "99") (name "unconnected-(F4A-PE11-Pad42)") (class "Default")
      (node (ref "F4") (pin "42") (pinfunction "PE11_42") (pintype "bidirectional"))
    )
    (net (code "100") (name "unconnected-(F4A-PE12-Pad43)") (class "Default")
      (node (ref "F4") (pin "43") (pinfunction "PE12_43") (pintype "bidirectional"))
    )
    (net (code "101") (name "unconnected-(F4A-PE13-Pad44)") (class "Default")
      (node (ref "F4") (pin "44") (pinfunction "PE13_44") (pintype "bidirectional"))
    )
    (net (code "102") (name "unconnected-(F4A-PE14-Pad45)") (class "Default")
      (node (ref "F4") (pin "45") (pinfunction "PE14_45") (pintype "bidirectional"))
    )
    (net (code "103") (name "unconnected-(F4B-VBAT-Pad6)") (class "Default")
      (node (ref "F4") (pin "6") (pinfunction "VBAT_6") (pintype "power_in"))
    )
    (net (code "104") (name "unconnected-(RC-Pad6)") (class "Default")
      (node (ref "RC") (pin "6") (pinfunction "6_6") (pintype "passive+no_connect"))
    )
    (net (code "105") (name "unconnected-(RC-Pad7)") (class "Default")
      (node (ref "RC") (pin "7") (pinfunction "7_7") (pintype "passive+no_connect"))
    )
    (net (code "106") (name "unconnected-(RC-Pad8)") (class "Default")
      (node (ref "RC") (pin "8") (pinfunction "8_8") (pintype "passive+no_connect"))
    )
    (net (code "107") (name "unconnected-(RC-Pad10)") (class "Default")
      (node (ref "RC") (pin "10") (pinfunction "10_10") (pintype "passive+no_connect"))
    )
    (net (code "108") (name "unconnected-(RC-Pad11)") (class "Default")
      (node (ref "RC") (pin "11") (pinfunction "11_11") (pintype "passive+no_connect"))
    )
    (net (code "109") (name "unconnected-(RC-Pad12)") (class "Default")
      (node (ref "RC") (pin "12") (pinfunction "12_12") (pintype "passive+no_connect"))
    )
    (net (code "110") (name "unconnected-(RC-Pad13)") (class "Default")
      (node (ref "RC") (pin "13") (pinfunction "13_13") (pintype "passive+no_connect"))
    )
    (net (code "111") (name "unconnected-(RC-Pad14)") (class "Default")
      (node (ref "RC") (pin "14") (pinfunction "14_14") (pintype "passive+no_connect"))
    )
    (net (code "112") (name "unconnected-(RC-Pad15)") (class "Default")
      (node (ref "RC") (pin "15") (pinfunction "15_15") (pintype "passive+no_connect"))
    )
    (net (code "113") (name "unconnected-(RC-Pad16)") (class "Default")
      (node (ref "RC") (pin "16") (pinfunction "16_16") (pintype "passive+no_connect"))
    )
    (net (code "114") (name "unconnected-(Uart-Pad2)") (class "Default")
      (node (ref "Uart") (pin "2") (pinfunction "2_2") (pintype "passive"))
    )
    (net (code "115") (name "unconnected-(Uart-Pad3)") (class "Default")
      (node (ref "Uart") (pin "3") (pinfunction "3_3") (pintype "passive"))
    )
    (net (code "116") (name "unconnected-(VL53-Pad2)") (class "Default")
      (node (ref "VL53") (pin "2") (pinfunction "2_2") (pintype "passive"))
    )
    (net (code "117") (name "unconnected-(VL53-Pad3)") (class "Default")
      (node (ref "VL53") (pin "3") (pinfunction "3_3") (pintype "passive"))
    )
  )
)
